# SparkFun_decade_resistance_box.net
KiCad netlist of a schematic drawn in EAGLE
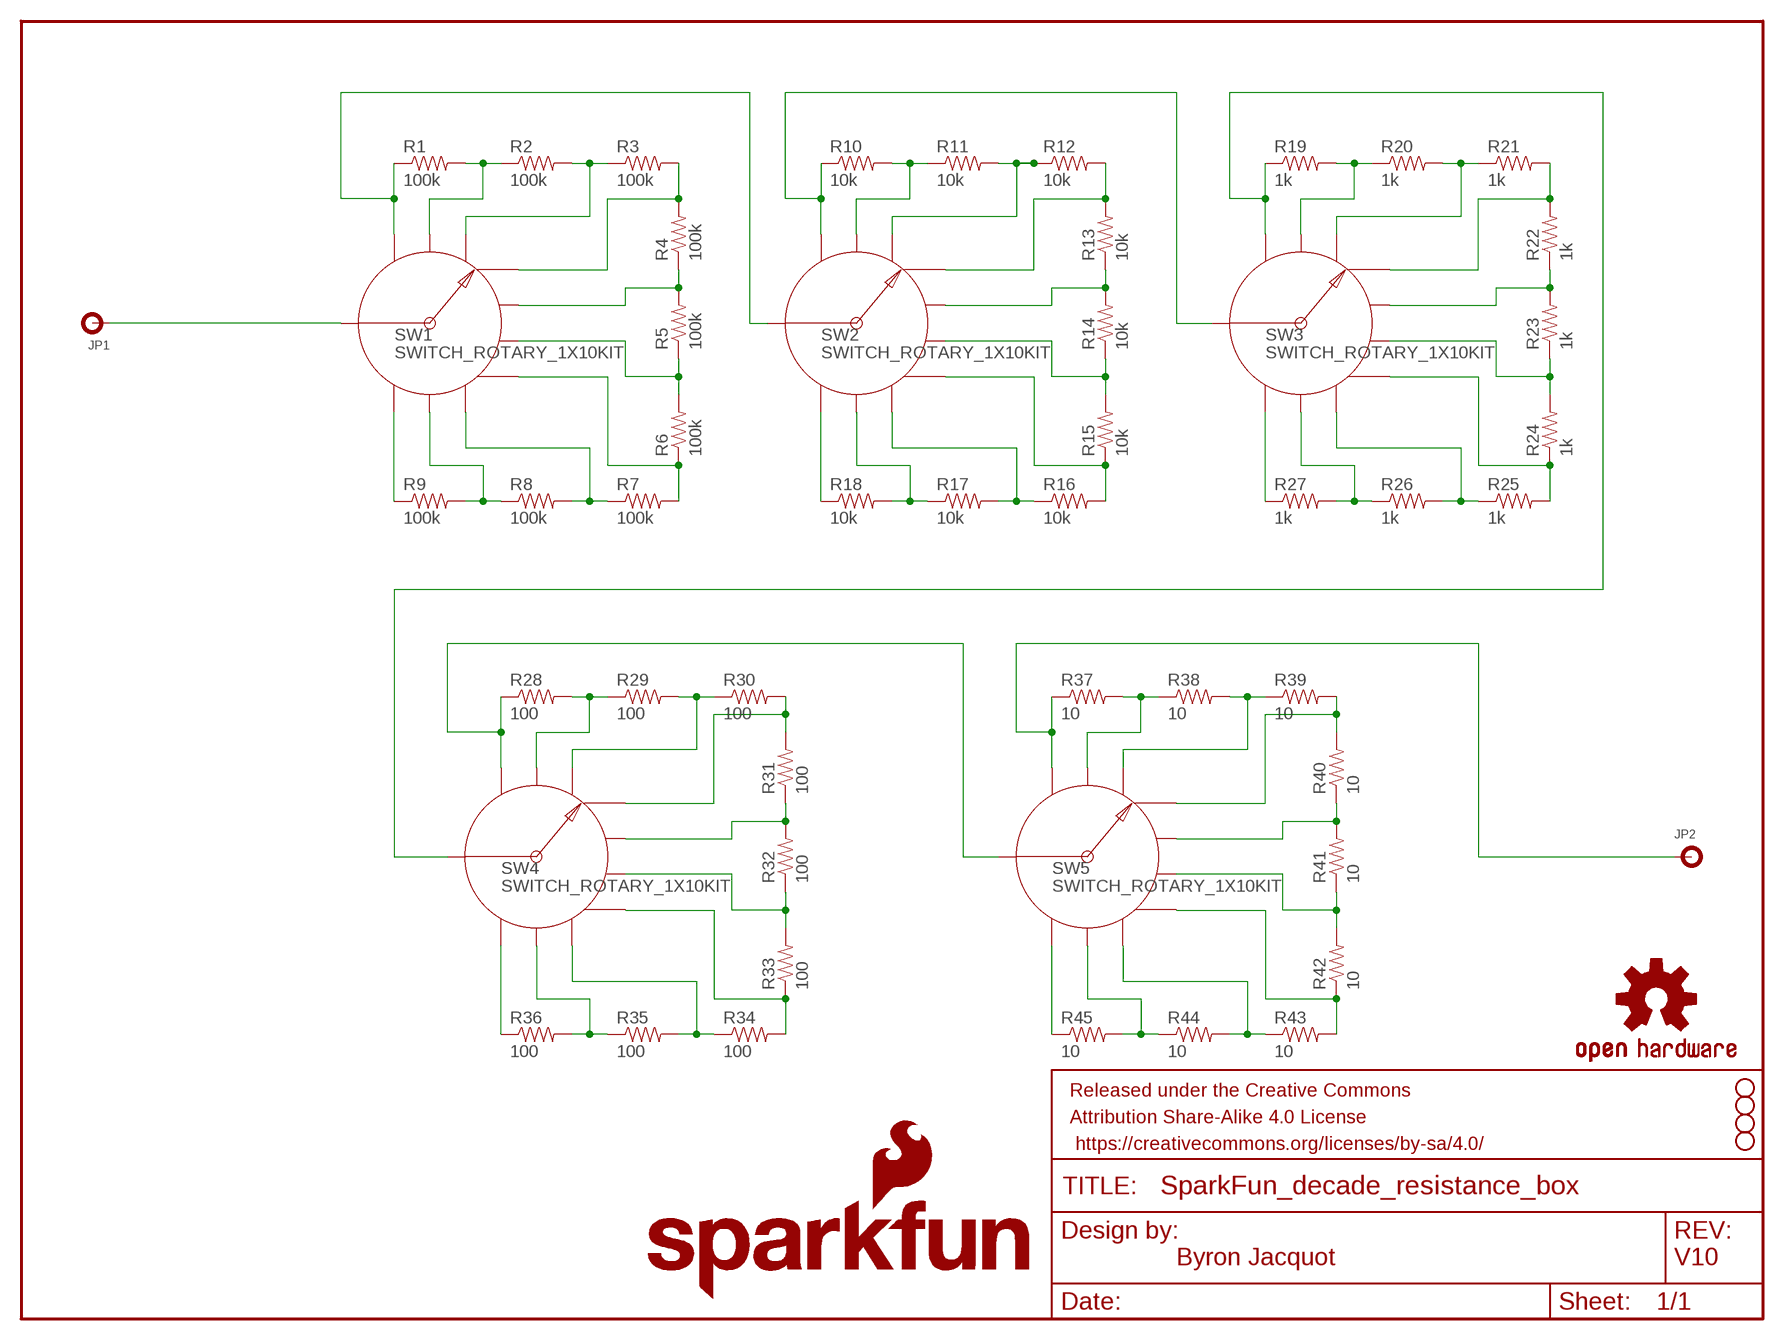
[diagram p0: schematic, sheet 1]

(export (version "E")
  (design (tool "Eeschema 10.0.6"))
  (components
    (comp (ref "FRAME1")
      (value "FRAME-LETTER")
      (footprint "eagle-import:CREATIVE_COMMONS")
      (libsource (lib "eagle-import") (part "FRAME-LETTER"))
    )
    (comp (ref "JP1")
      (value "BANANA-JACK")
      (footprint "eagle-import:BANANA-JACK")
      (libsource (lib "eagle-import") (part "BANANA-JACK"))
    )
    (comp (ref "JP2")
      (value "BANANA-JACK")
      (footprint "eagle-import:BANANA-JACK")
      (libsource (lib "eagle-import") (part "BANANA-JACK"))
    )
    (comp (ref "LOGO1")
      (value "OSHW-LOGOL")
      (footprint "eagle-import:OSHW-LOGO-L")
      (libsource (lib "eagle-import") (part "OSHW-LOGOL"))
    )
    (comp (ref "LOGO2")
      (value "SFE_LOGO_NAME_FLAME.2_INCH")
      (footprint "eagle-import:SFE_LOGO_NAME_FLAME_.2")
      (libsource (lib "eagle-import") (part "SFE_LOGO_NAME_FLAME.2_INCH"))
    )
    (comp (ref "LOGO3")
      (value "SFE_LOGO_NAME_FLAME.5_INCH")
      (footprint "eagle-import:SFE_LOGO_NAME_FLAME_.5")
      (libsource (lib "eagle-import") (part "SFE_LOGO_NAME_FLAME.5_INCH"))
    )
    (comp (ref "LOGO4")
      (value "OSHW-LOGOL")
      (footprint "eagle-import:OSHW-LOGO-L")
      (libsource (lib "eagle-import") (part "OSHW-LOGOL"))
    )
    (comp (ref "R1")
      (value "100k")
      (footprint "eagle-import:AXIAL-0.1EZ")
      (libsource (lib "eagle-import") (part "100KOHM-1/4W-1%(PTH)VERT-KIT"))
    )
    (comp (ref "R2")
      (value "100k")
      (footprint "eagle-import:AXIAL-0.1EZ")
      (libsource (lib "eagle-import") (part "100KOHM-1/4W-1%(PTH)VERT-KIT"))
    )
    (comp (ref "R3")
      (value "100k")
      (footprint "eagle-import:AXIAL-0.1EZ")
      (libsource (lib "eagle-import") (part "100KOHM-1/4W-1%(PTH)VERT-KIT"))
    )
    (comp (ref "R4")
      (value "100k")
      (footprint "eagle-import:AXIAL-0.1EZ")
      (libsource (lib "eagle-import") (part "100KOHM-1/4W-1%(PTH)VERT-KIT"))
    )
    (comp (ref "R5")
      (value "100k")
      (footprint "eagle-import:AXIAL-0.1EZ")
      (libsource (lib "eagle-import") (part "100KOHM-1/4W-1%(PTH)VERT-KIT"))
    )
    (comp (ref "R6")
      (value "100k")
      (footprint "eagle-import:AXIAL-0.1EZ")
      (libsource (lib "eagle-import") (part "100KOHM-1/4W-1%(PTH)VERT-KIT"))
    )
    (comp (ref "R7")
      (value "100k")
      (footprint "eagle-import:AXIAL-0.1EZ")
      (libsource (lib "eagle-import") (part "100KOHM-1/4W-1%(PTH)VERT-KIT"))
    )
    (comp (ref "R8")
      (value "100k")
      (footprint "eagle-import:AXIAL-0.1EZ")
      (libsource (lib "eagle-import") (part "100KOHM-1/4W-1%(PTH)VERT-KIT"))
    )
    (comp (ref "R9")
      (value "100k")
      (footprint "eagle-import:AXIAL-0.1EZ")
      (libsource (lib "eagle-import") (part "100KOHM-1/4W-1%(PTH)VERT-KIT"))
    )
    (comp (ref "R10")
      (value "10k")
      (footprint "eagle-import:AXIAL-0.1EZ")
      (libsource (lib "eagle-import") (part "10KOHM-1/4W-1%(PTH)VERT-KIT"))
    )
    (comp (ref "R11")
      (value "10k")
      (footprint "eagle-import:AXIAL-0.1EZ")
      (libsource (lib "eagle-import") (part "10KOHM-1/4W-1%(PTH)VERT-KIT"))
    )
    (comp (ref "R12")
      (value "10k")
      (footprint "eagle-import:AXIAL-0.1EZ")
      (libsource (lib "eagle-import") (part "10KOHM-1/4W-1%(PTH)VERT-KIT"))
    )
    (comp (ref "R13")
      (value "10k")
      (footprint "eagle-import:AXIAL-0.1EZ")
      (libsource (lib "eagle-import") (part "10KOHM-1/4W-1%(PTH)VERT-KIT"))
    )
    (comp (ref "R14")
      (value "10k")
      (footprint "eagle-import:AXIAL-0.1EZ")
      (libsource (lib "eagle-import") (part "10KOHM-1/4W-1%(PTH)VERT-KIT"))
    )
    (comp (ref "R15")
      (value "10k")
      (footprint "eagle-import:AXIAL-0.1EZ")
      (libsource (lib "eagle-import") (part "10KOHM-1/4W-1%(PTH)VERT-KIT"))
    )
    (comp (ref "R16")
      (value "10k")
      (footprint "eagle-import:AXIAL-0.1EZ")
      (libsource (lib "eagle-import") (part "10KOHM-1/4W-1%(PTH)VERT-KIT"))
    )
    (comp (ref "R17")
      (value "10k")
      (footprint "eagle-import:AXIAL-0.1EZ")
      (libsource (lib "eagle-import") (part "10KOHM-1/4W-1%(PTH)VERT-KIT"))
    )
    (comp (ref "R18")
      (value "10k")
      (footprint "eagle-import:AXIAL-0.1EZ")
      (libsource (lib "eagle-import") (part "10KOHM-1/4W-1%(PTH)VERT-KIT"))
    )
    (comp (ref "R19")
      (value "1k")
      (footprint "eagle-import:AXIAL-0.1EZ")
      (libsource (lib "eagle-import") (part "1KOHM-1/4W-1%(PTH)VERT-KIT"))
    )
    (comp (ref "R20")
      (value "1k")
      (footprint "eagle-import:AXIAL-0.1EZ")
      (libsource (lib "eagle-import") (part "1KOHM-1/4W-1%(PTH)VERT-KIT"))
    )
    (comp (ref "R21")
      (value "1k")
      (footprint "eagle-import:AXIAL-0.1EZ")
      (libsource (lib "eagle-import") (part "1KOHM-1/4W-1%(PTH)VERT-KIT"))
    )
    (comp (ref "R22")
      (value "1k")
      (footprint "eagle-import:AXIAL-0.1EZ")
      (libsource (lib "eagle-import") (part "1KOHM-1/4W-1%(PTH)VERT-KIT"))
    )
    (comp (ref "R23")
      (value "1k")
      (footprint "eagle-import:AXIAL-0.1EZ")
      (libsource (lib "eagle-import") (part "1KOHM-1/4W-1%(PTH)VERT-KIT"))
    )
    (comp (ref "R24")
      (value "1k")
      (footprint "eagle-import:AXIAL-0.1EZ")
      (libsource (lib "eagle-import") (part "1KOHM-1/4W-1%(PTH)VERT-KIT"))
    )
    (comp (ref "R25")
      (value "1k")
      (footprint "eagle-import:AXIAL-0.1EZ")
      (libsource (lib "eagle-import") (part "1KOHM-1/4W-1%(PTH)VERT-KIT"))
    )
    (comp (ref "R26")
      (value "1k")
      (footprint "eagle-import:AXIAL-0.1EZ")
      (libsource (lib "eagle-import") (part "1KOHM-1/4W-1%(PTH)VERT-KIT"))
    )
    (comp (ref "R27")
      (value "1k")
      (footprint "eagle-import:AXIAL-0.1EZ")
      (libsource (lib "eagle-import") (part "1KOHM-1/4W-1%(PTH)VERT-KIT"))
    )
    (comp (ref "R28")
      (value "100")
      (footprint "eagle-import:AXIAL-0.1EZ")
      (libsource (lib "eagle-import") (part "100OHM-1/4W-1%(PTH)VERT-KIT"))
    )
    (comp (ref "R29")
      (value "100")
      (footprint "eagle-import:AXIAL-0.1EZ")
      (libsource (lib "eagle-import") (part "100OHM-1/4W-1%(PTH)VERT-KIT"))
    )
    (comp (ref "R30")
      (value "100")
      (footprint "eagle-import:AXIAL-0.1EZ")
      (libsource (lib "eagle-import") (part "100OHM-1/4W-1%(PTH)VERT-KIT"))
    )
    (comp (ref "R31")
      (value "100")
      (footprint "eagle-import:AXIAL-0.1EZ")
      (libsource (lib "eagle-import") (part "100OHM-1/4W-1%(PTH)VERT-KIT"))
    )
    (comp (ref "R32")
      (value "100")
      (footprint "eagle-import:AXIAL-0.1EZ")
      (libsource (lib "eagle-import") (part "100OHM-1/4W-1%(PTH)VERT-KIT"))
    )
    (comp (ref "R33")
      (value "100")
      (footprint "eagle-import:AXIAL-0.1EZ")
      (libsource (lib "eagle-import") (part "100OHM-1/4W-1%(PTH)VERT-KIT"))
    )
    (comp (ref "R34")
      (value "100")
      (footprint "eagle-import:AXIAL-0.1EZ")
      (libsource (lib "eagle-import") (part "100OHM-1/4W-1%(PTH)VERT-KIT"))
    )
    (comp (ref "R35")
      (value "100")
      (footprint "eagle-import:AXIAL-0.1EZ")
      (libsource (lib "eagle-import") (part "100OHM-1/4W-1%(PTH)VERT-KIT"))
    )
    (comp (ref "R36")
      (value "100")
      (footprint "eagle-import:AXIAL-0.1EZ")
      (libsource (lib "eagle-import") (part "100OHM-1/4W-1%(PTH)VERT-KIT"))
    )
    (comp (ref "R37")
      (value "10")
      (footprint "eagle-import:AXIAL-0.1EZ")
      (libsource (lib "eagle-import") (part "10OHM-1/4W-1%(PTH)VERT-KIT"))
    )
    (comp (ref "R38")
      (value "10")
      (footprint "eagle-import:AXIAL-0.1EZ")
      (libsource (lib "eagle-import") (part "10OHM-1/4W-1%(PTH)VERT-KIT"))
    )
    (comp (ref "R39")
      (value "10")
      (footprint "eagle-import:AXIAL-0.1EZ")
      (libsource (lib "eagle-import") (part "10OHM-1/4W-1%(PTH)VERT-KIT"))
    )
    (comp (ref "R40")
      (value "10")
      (footprint "eagle-import:AXIAL-0.1EZ")
      (libsource (lib "eagle-import") (part "10OHM-1/4W-1%(PTH)VERT-KIT"))
    )
    (comp (ref "R41")
      (value "10")
      (footprint "eagle-import:AXIAL-0.1EZ")
      (libsource (lib "eagle-import") (part "10OHM-1/4W-1%(PTH)VERT-KIT"))
    )
    (comp (ref "R42")
      (value "10")
      (footprint "eagle-import:AXIAL-0.1EZ")
      (libsource (lib "eagle-import") (part "10OHM-1/4W-1%(PTH)VERT-KIT"))
    )
    (comp (ref "R43")
      (value "10")
      (footprint "eagle-import:AXIAL-0.1EZ")
      (libsource (lib "eagle-import") (part "10OHM-1/4W-1%(PTH)VERT-KIT"))
    )
    (comp (ref "R44")
      (value "10")
      (footprint "eagle-import:AXIAL-0.1EZ")
      (libsource (lib "eagle-import") (part "10OHM-1/4W-1%(PTH)VERT-KIT"))
    )
    (comp (ref "R45")
      (value "10")
      (footprint "eagle-import:AXIAL-0.1EZ")
      (libsource (lib "eagle-import") (part "10OHM-1/4W-1%(PTH)VERT-KIT"))
    )
    (comp (ref "STANDOFF1")
      (value "STAND-OFF")
      (footprint "eagle-import:STAND-OFF")
      (libsource (lib "eagle-import") (part "STAND-OFF"))
    )
    (comp (ref "STANDOFF2")
      (value "STAND-OFF")
      (footprint "eagle-import:STAND-OFF")
      (libsource (lib "eagle-import") (part "STAND-OFF"))
    )
    (comp (ref "STANDOFF3")
      (value "STAND-OFF")
      (footprint "eagle-import:STAND-OFF")
      (libsource (lib "eagle-import") (part "STAND-OFF"))
    )
    (comp (ref "STANDOFF4")
      (value "STAND-OFF")
      (footprint "eagle-import:STAND-OFF")
      (libsource (lib "eagle-import") (part "STAND-OFF"))
    )
    (comp (ref "SW1")
      (value "SWITCH_ROTARY_1X10KIT")
      (footprint "eagle-import:ROTARY_SWITCH_1X10_KIT")
      (libsource (lib "eagle-import") (part "SWITCH_ROTARY_1X10KIT"))
    )
    (comp (ref "SW2")
      (value "SWITCH_ROTARY_1X10KIT")
      (footprint "eagle-import:ROTARY_SWITCH_1X10_KIT")
      (libsource (lib "eagle-import") (part "SWITCH_ROTARY_1X10KIT"))
    )
    (comp (ref "SW3")
      (value "SWITCH_ROTARY_1X10KIT")
      (footprint "eagle-import:ROTARY_SWITCH_1X10_KIT")
      (libsource (lib "eagle-import") (part "SWITCH_ROTARY_1X10KIT"))
    )
    (comp (ref "SW4")
      (value "SWITCH_ROTARY_1X10KIT")
      (footprint "eagle-import:ROTARY_SWITCH_1X10_KIT")
      (libsource (lib "eagle-import") (part "SWITCH_ROTARY_1X10KIT"))
    )
    (comp (ref "SW5")
      (value "SWITCH_ROTARY_1X10KIT")
      (footprint "eagle-import:ROTARY_SWITCH_1X10_KIT")
      (libsource (lib "eagle-import") (part "SWITCH_ROTARY_1X10KIT"))
    )
  )
  (nets
    (net (code "1") (name "Net-(JP1-PadP$1)") (class "Default")
      (node (ref "JP1") (pin "P$1") (pinfunction "P$1_P$1") (pintype "bidirectional"))
      (node (ref "SW1") (pin "COMMON") (pinfunction "COMMON_COMMON") (pintype "bidirectional"))
    )
    (net (code "2") (name "Net-(R1-1)") (class "Default")
      (node (ref "R1") (pin "P$1") (pinfunction "1_P$1") (pintype "passive"))
      (node (ref "SW1") (pin "1") (pinfunction "1_1") (pintype "bidirectional"))
      (node (ref "SW2") (pin "COMMON") (pinfunction "COMMON_COMMON") (pintype "bidirectional"))
    )
    (net (code "3") (name "Net-(R1-2)") (class "Default")
      (node (ref "R1") (pin "P$2") (pinfunction "2_P$2") (pintype "passive"))
      (node (ref "R2") (pin "P$1") (pinfunction "1_P$1") (pintype "passive"))
      (node (ref "SW1") (pin "2") (pinfunction "2_2") (pintype "bidirectional"))
    )
    (net (code "4") (name "Net-(R2-2)") (class "Default")
      (node (ref "R2") (pin "P$2") (pinfunction "2_P$2") (pintype "passive"))
      (node (ref "R3") (pin "P$1") (pinfunction "1_P$1") (pintype "passive"))
      (node (ref "SW1") (pin "3") (pinfunction "3_3") (pintype "bidirectional"))
    )
    (net (code "5") (name "Net-(R3-2)") (class "Default")
      (node (ref "R3") (pin "P$2") (pinfunction "2_P$2") (pintype "passive"))
      (node (ref "R4") (pin "P$2") (pinfunction "2_P$2") (pintype "passive"))
      (node (ref "SW1") (pin "4") (pinfunction "4_4") (pintype "bidirectional"))
    )
    (net (code "6") (name "Net-(R4-1)") (class "Default")
      (node (ref "R4") (pin "P$1") (pinfunction "1_P$1") (pintype "passive"))
      (node (ref "R5") (pin "P$2") (pinfunction "2_P$2") (pintype "passive"))
      (node (ref "SW1") (pin "5") (pinfunction "5_5") (pintype "bidirectional"))
    )
    (net (code "7") (name "Net-(R5-1)") (class "Default")
      (node (ref "R5") (pin "P$1") (pinfunction "1_P$1") (pintype "passive"))
      (node (ref "R6") (pin "P$2") (pinfunction "2_P$2") (pintype "passive"))
      (node (ref "SW1") (pin "6") (pinfunction "6_6") (pintype "bidirectional"))
    )
    (net (code "8") (name "Net-(R6-1)") (class "Default")
      (node (ref "R6") (pin "P$1") (pinfunction "1_P$1") (pintype "passive"))
      (node (ref "R7") (pin "P$2") (pinfunction "2_P$2") (pintype "passive"))
      (node (ref "SW1") (pin "7") (pinfunction "7_7") (pintype "bidirectional"))
    )
    (net (code "9") (name "Net-(R7-1)") (class "Default")
      (node (ref "R7") (pin "P$1") (pinfunction "1_P$1") (pintype "passive"))
      (node (ref "R8") (pin "P$2") (pinfunction "2_P$2") (pintype "passive"))
      (node (ref "SW1") (pin "8") (pinfunction "8_8") (pintype "bidirectional"))
    )
    (net (code "10") (name "Net-(R8-1)") (class "Default")
      (node (ref "R8") (pin "P$1") (pinfunction "1_P$1") (pintype "passive"))
      (node (ref "R9") (pin "P$2") (pinfunction "2_P$2") (pintype "passive"))
      (node (ref "SW1") (pin "9") (pinfunction "9_9") (pintype "bidirectional"))
    )
    (net (code "11") (name "Net-(R9-1)") (class "Default")
      (node (ref "R9") (pin "P$1") (pinfunction "1_P$1") (pintype "passive"))
      (node (ref "SW1") (pin "10") (pinfunction "10_10") (pintype "bidirectional"))
    )
    (net (code "12") (name "Net-(R10-1)") (class "Default")
      (node (ref "R10") (pin "P$1") (pinfunction "1_P$1") (pintype "passive"))
      (node (ref "SW2") (pin "1") (pinfunction "1_1") (pintype "bidirectional"))
      (node (ref "SW3") (pin "COMMON") (pinfunction "COMMON_COMMON") (pintype "bidirectional"))
    )
    (net (code "13") (name "Net-(R10-2)") (class "Default")
      (node (ref "R10") (pin "P$2") (pinfunction "2_P$2") (pintype "passive"))
      (node (ref "R11") (pin "P$1") (pinfunction "1_P$1") (pintype "passive"))
      (node (ref "SW2") (pin "2") (pinfunction "2_2") (pintype "bidirectional"))
    )
    (net (code "14") (name "Net-(R11-2)") (class "Default")
      (node (ref "R11") (pin "P$2") (pinfunction "2_P$2") (pintype "passive"))
      (node (ref "R12") (pin "P$1") (pinfunction "1_P$1") (pintype "passive"))
      (node (ref "SW2") (pin "3") (pinfunction "3_3") (pintype "bidirectional"))
    )
    (net (code "15") (name "Net-(R12-2)") (class "Default")
      (node (ref "R12") (pin "P$2") (pinfunction "2_P$2") (pintype "passive"))
      (node (ref "R13") (pin "P$2") (pinfunction "2_P$2") (pintype "passive"))
      (node (ref "SW2") (pin "4") (pinfunction "4_4") (pintype "bidirectional"))
    )
    (net (code "16") (name "Net-(R13-1)") (class "Default")
      (node (ref "R13") (pin "P$1") (pinfunction "1_P$1") (pintype "passive"))
      (node (ref "R14") (pin "P$2") (pinfunction "2_P$2") (pintype "passive"))
      (node (ref "SW2") (pin "5") (pinfunction "5_5") (pintype "bidirectional"))
    )
    (net (code "17") (name "Net-(R14-1)") (class "Default")
      (node (ref "R14") (pin "P$1") (pinfunction "1_P$1") (pintype "passive"))
      (node (ref "R15") (pin "P$2") (pinfunction "2_P$2") (pintype "passive"))
      (node (ref "SW2") (pin "6") (pinfunction "6_6") (pintype "bidirectional"))
    )
    (net (code "18") (name "Net-(R15-1)") (class "Default")
      (node (ref "R15") (pin "P$1") (pinfunction "1_P$1") (pintype "passive"))
      (node (ref "R16") (pin "P$2") (pinfunction "2_P$2") (pintype "passive"))
      (node (ref "SW2") (pin "7") (pinfunction "7_7") (pintype "bidirectional"))
    )
    (net (code "19") (name "Net-(R16-1)") (class "Default")
      (node (ref "R16") (pin "P$1") (pinfunction "1_P$1") (pintype "passive"))
      (node (ref "R17") (pin "P$2") (pinfunction "2_P$2") (pintype "passive"))
      (node (ref "SW2") (pin "8") (pinfunction "8_8") (pintype "bidirectional"))
    )
    (net (code "20") (name "Net-(R17-1)") (class "Default")
      (node (ref "R17") (pin "P$1") (pinfunction "1_P$1") (pintype "passive"))
      (node (ref "R18") (pin "P$2") (pinfunction "2_P$2") (pintype "passive"))
      (node (ref "SW2") (pin "9") (pinfunction "9_9") (pintype "bidirectional"))
    )
    (net (code "21") (name "Net-(R18-1)") (class "Default")
      (node (ref "R18") (pin "P$1") (pinfunction "1_P$1") (pintype "passive"))
      (node (ref "SW2") (pin "10") (pinfunction "10_10") (pintype "bidirectional"))
    )
    (net (code "22") (name "Net-(R19-1)") (class "Default")
      (node (ref "R19") (pin "P$1") (pinfunction "1_P$1") (pintype "passive"))
      (node (ref "SW3") (pin "1") (pinfunction "1_1") (pintype "bidirectional"))
      (node (ref "SW4") (pin "COMMON") (pinfunction "COMMON_COMMON") (pintype "bidirectional"))
    )
    (net (code "23") (name "Net-(R19-2)") (class "Default")
      (node (ref "R19") (pin "P$2") (pinfunction "2_P$2") (pintype "passive"))
      (node (ref "R20") (pin "P$1") (pinfunction "1_P$1") (pintype "passive"))
      (node (ref "SW3") (pin "2") (pinfunction "2_2") (pintype "bidirectional"))
    )
    (net (code "24") (name "Net-(R20-2)") (class "Default")
      (node (ref "R20") (pin "P$2") (pinfunction "2_P$2") (pintype "passive"))
      (node (ref "R21") (pin "P$1") (pinfunction "1_P$1") (pintype "passive"))
      (node (ref "SW3") (pin "3") (pinfunction "3_3") (pintype "bidirectional"))
    )
    (net (code "25") (name "Net-(R21-2)") (class "Default")
      (node (ref "R21") (pin "P$2") (pinfunction "2_P$2") (pintype "passive"))
      (node (ref "R22") (pin "P$2") (pinfunction "2_P$2") (pintype "passive"))
      (node (ref "SW3") (pin "4") (pinfunction "4_4") (pintype "bidirectional"))
    )
    (net (code "26") (name "Net-(R22-1)") (class "Default")
      (node (ref "R22") (pin "P$1") (pinfunction "1_P$1") (pintype "passive"))
      (node (ref "R23") (pin "P$2") (pinfunction "2_P$2") (pintype "passive"))
      (node (ref "SW3") (pin "5") (pinfunction "5_5") (pintype "bidirectional"))
    )
    (net (code "27") (name "Net-(R23-1)") (class "Default")
      (node (ref "R23") (pin "P$1") (pinfunction "1_P$1") (pintype "passive"))
      (node (ref "R24") (pin "P$2") (pinfunction "2_P$2") (pintype "passive"))
      (node (ref "SW3") (pin "6") (pinfunction "6_6") (pintype "bidirectional"))
    )
    (net (code "28") (name "Net-(R24-1)") (class "Default")
      (node (ref "R24") (pin "P$1") (pinfunction "1_P$1") (pintype "passive"))
      (node (ref "R25") (pin "P$2") (pinfunction "2_P$2") (pintype "passive"))
      (node (ref "SW3") (pin "7") (pinfunction "7_7") (pintype "bidirectional"))
    )
    (net (code "29") (name "Net-(R25-1)") (class "Default")
      (node (ref "R25") (pin "P$1") (pinfunction "1_P$1") (pintype "passive"))
      (node (ref "R26") (pin "P$2") (pinfunction "2_P$2") (pintype "passive"))
      (node (ref "SW3") (pin "8") (pinfunction "8_8") (pintype "bidirectional"))
    )
    (net (code "30") (name "Net-(R26-1)") (class "Default")
      (node (ref "R26") (pin "P$1") (pinfunction "1_P$1") (pintype "passive"))
      (node (ref "R27") (pin "P$2") (pinfunction "2_P$2") (pintype "passive"))
      (node (ref "SW3") (pin "9") (pinfunction "9_9") (pintype "bidirectional"))
    )
    (net (code "31") (name "Net-(R27-1)") (class "Default")
      (node (ref "R27") (pin "P$1") (pinfunction "1_P$1") (pintype "passive"))
      (node (ref "SW3") (pin "10") (pinfunction "10_10") (pintype "bidirectional"))
    )
    (net (code "32") (name "Net-(R28-1)") (class "Default")
      (node (ref "R28") (pin "P$1") (pinfunction "1_P$1") (pintype "passive"))
      (node (ref "SW4") (pin "1") (pinfunction "1_1") (pintype "bidirectional"))
      (node (ref "SW5") (pin "COMMON") (pinfunction "COMMON_COMMON") (pintype "bidirectional"))
    )
    (net (code "33") (name "Net-(R28-2)") (class "Default")
      (node (ref "R28") (pin "P$2") (pinfunction "2_P$2") (pintype "passive"))
      (node (ref "R29") (pin "P$1") (pinfunction "1_P$1") (pintype "passive"))
      (node (ref "SW4") (pin "2") (pinfunction "2_2") (pintype "bidirectional"))
    )
    (net (code "34") (name "Net-(R29-2)") (class "Default")
      (node (ref "R29") (pin "P$2") (pinfunction "2_P$2") (pintype "passive"))
      (node (ref "R30") (pin "P$1") (pinfunction "1_P$1") (pintype "passive"))
      (node (ref "SW4") (pin "3") (pinfunction "3_3") (pintype "bidirectional"))
    )
    (net (code "35") (name "Net-(R30-2)") (class "Default")
      (node (ref "R30") (pin "P$2") (pinfunction "2_P$2") (pintype "passive"))
      (node (ref "R31") (pin "P$2") (pinfunction "2_P$2") (pintype "passive"))
      (node (ref "SW4") (pin "4") (pinfunction "4_4") (pintype "bidirectional"))
    )
    (net (code "36") (name "Net-(R31-1)") (class "Default")
      (node (ref "R31") (pin "P$1") (pinfunction "1_P$1") (pintype "passive"))
      (node (ref "R32") (pin "P$2") (pinfunction "2_P$2") (pintype "passive"))
      (node (ref "SW4") (pin "5") (pinfunction "5_5") (pintype "bidirectional"))
    )
    (net (code "37") (name "Net-(R32-1)") (class "Default")
      (node (ref "R32") (pin "P$1") (pinfunction "1_P$1") (pintype "passive"))
      (node (ref "R33") (pin "P$2") (pinfunction "2_P$2") (pintype "passive"))
      (node (ref "SW4") (pin "6") (pinfunction "6_6") (pintype "bidirectional"))
    )
    (net (code "38") (name "Net-(R33-1)") (class "Default")
      (node (ref "R33") (pin "P$1") (pinfunction "1_P$1") (pintype "passive"))
      (node (ref "R34") (pin "P$2") (pinfunction "2_P$2") (pintype "passive"))
      (node (ref "SW4") (pin "7") (pinfunction "7_7") (pintype "bidirectional"))
    )
    (net (code "39") (name "Net-(R34-1)") (class "Default")
      (node (ref "R34") (pin "P$1") (pinfunction "1_P$1") (pintype "passive"))
      (node (ref "R35") (pin "P$2") (pinfunction "2_P$2") (pintype "passive"))
      (node (ref "SW4") (pin "8") (pinfunction "8_8") (pintype "bidirectional"))
    )
    (net (code "40") (name "Net-(R35-1)") (class "Default")
      (node (ref "R35") (pin "P$1") (pinfunction "1_P$1") (pintype "passive"))
      (node (ref "R36") (pin "P$2") (pinfunction "2_P$2") (pintype "passive"))
      (node (ref "SW4") (pin "9") (pinfunction "9_9") (pintype "bidirectional"))
    )
    (net (code "41") (name "Net-(R36-1)") (class "Default")
      (node (ref "R36") (pin "P$1") (pinfunction "1_P$1") (pintype "passive"))
      (node (ref "SW4") (pin "10") (pinfunction "10_10") (pintype "bidirectional"))
    )
    (net (code "42") (name "Net-(R37-1)") (class "Default")
      (node (ref "JP2") (pin "P$1") (pinfunction "P$1_P$1") (pintype "bidirectional"))
      (node (ref "R37") (pin "P$1") (pinfunction "1_P$1") (pintype "passive"))
      (node (ref "SW5") (pin "1") (pinfunction "1_1") (pintype "bidirectional"))
    )
    (net (code "43") (name "Net-(R37-2)") (class "Default")
      (node (ref "R37") (pin "P$2") (pinfunction "2_P$2") (pintype "passive"))
      (node (ref "R38") (pin "P$1") (pinfunction "1_P$1") (pintype "passive"))
      (node (ref "SW5") (pin "2") (pinfunction "2_2") (pintype "bidirectional"))
    )
    (net (code "44") (name "Net-(R38-2)") (class "Default")
      (node (ref "R38") (pin "P$2") (pinfunction "2_P$2") (pintype "passive"))
      (node (ref "R39") (pin "P$1") (pinfunction "1_P$1") (pintype "passive"))
      (node (ref "SW5") (pin "3") (pinfunction "3_3") (pintype "bidirectional"))
    )
    (net (code "45") (name "Net-(R39-2)") (class "Default")
      (node (ref "R39") (pin "P$2") (pinfunction "2_P$2") (pintype "passive"))
      (node (ref "R40") (pin "P$2") (pinfunction "2_P$2") (pintype "passive"))
      (node (ref "SW5") (pin "4") (pinfunction "4_4") (pintype "bidirectional"))
    )
    (net (code "46") (name "Net-(R40-1)") (class "Default")
      (node (ref "R40") (pin "P$1") (pinfunction "1_P$1") (pintype "passive"))
      (node (ref "R41") (pin "P$2") (pinfunction "2_P$2") (pintype "passive"))
      (node (ref "SW5") (pin "5") (pinfunction "5_5") (pintype "bidirectional"))
    )
    (net (code "47") (name "Net-(R41-1)") (class "Default")
      (node (ref "R41") (pin "P$1") (pinfunction "1_P$1") (pintype "passive"))
      (node (ref "R42") (pin "P$2") (pinfunction "2_P$2") (pintype "passive"))
      (node (ref "SW5") (pin "6") (pinfunction "6_6") (pintype "bidirectional"))
    )
    (net (code "48") (name "Net-(R42-1)") (class "Default")
      (node (ref "R42") (pin "P$1") (pinfunction "1_P$1") (pintype "passive"))
      (node (ref "R43") (pin "P$2") (pinfunction "2_P$2") (pintype "passive"))
      (node (ref "SW5") (pin "7") (pinfunction "7_7") (pintype "bidirectional"))
    )
    (net (code "49") (name "Net-(R43-1)") (class "Default")
      (node (ref "R43") (pin "P$1") (pinfunction "1_P$1") (pintype "passive"))
      (node (ref "R44") (pin "P$2") (pinfunction "2_P$2") (pintype "passive"))
      (node (ref "SW5") (pin "8") (pinfunction "8_8") (pintype "bidirectional"))
    )
    (net (code "50") (name "Net-(R44-1)") (class "Default")
      (node (ref "R44") (pin "P$1") (pinfunction "1_P$1") (pintype "passive"))
      (node (ref "R45") (pin "P$2") (pinfunction "2_P$2") (pintype "passive"))
      (node (ref "SW5") (pin "9") (pinfunction "9_9") (pintype "bidirectional"))
    )
    (net (code "51") (name "Net-(R45-1)") (class "Default")
      (node (ref "R45") (pin "P$1") (pinfunction "1_P$1") (pintype "passive"))
      (node (ref "SW5") (pin "10") (pinfunction "10_10") (pintype "bidirectional"))
    )
  )
)
